# power.net
KiCad netlist of a schematic drawn in Altium Designer
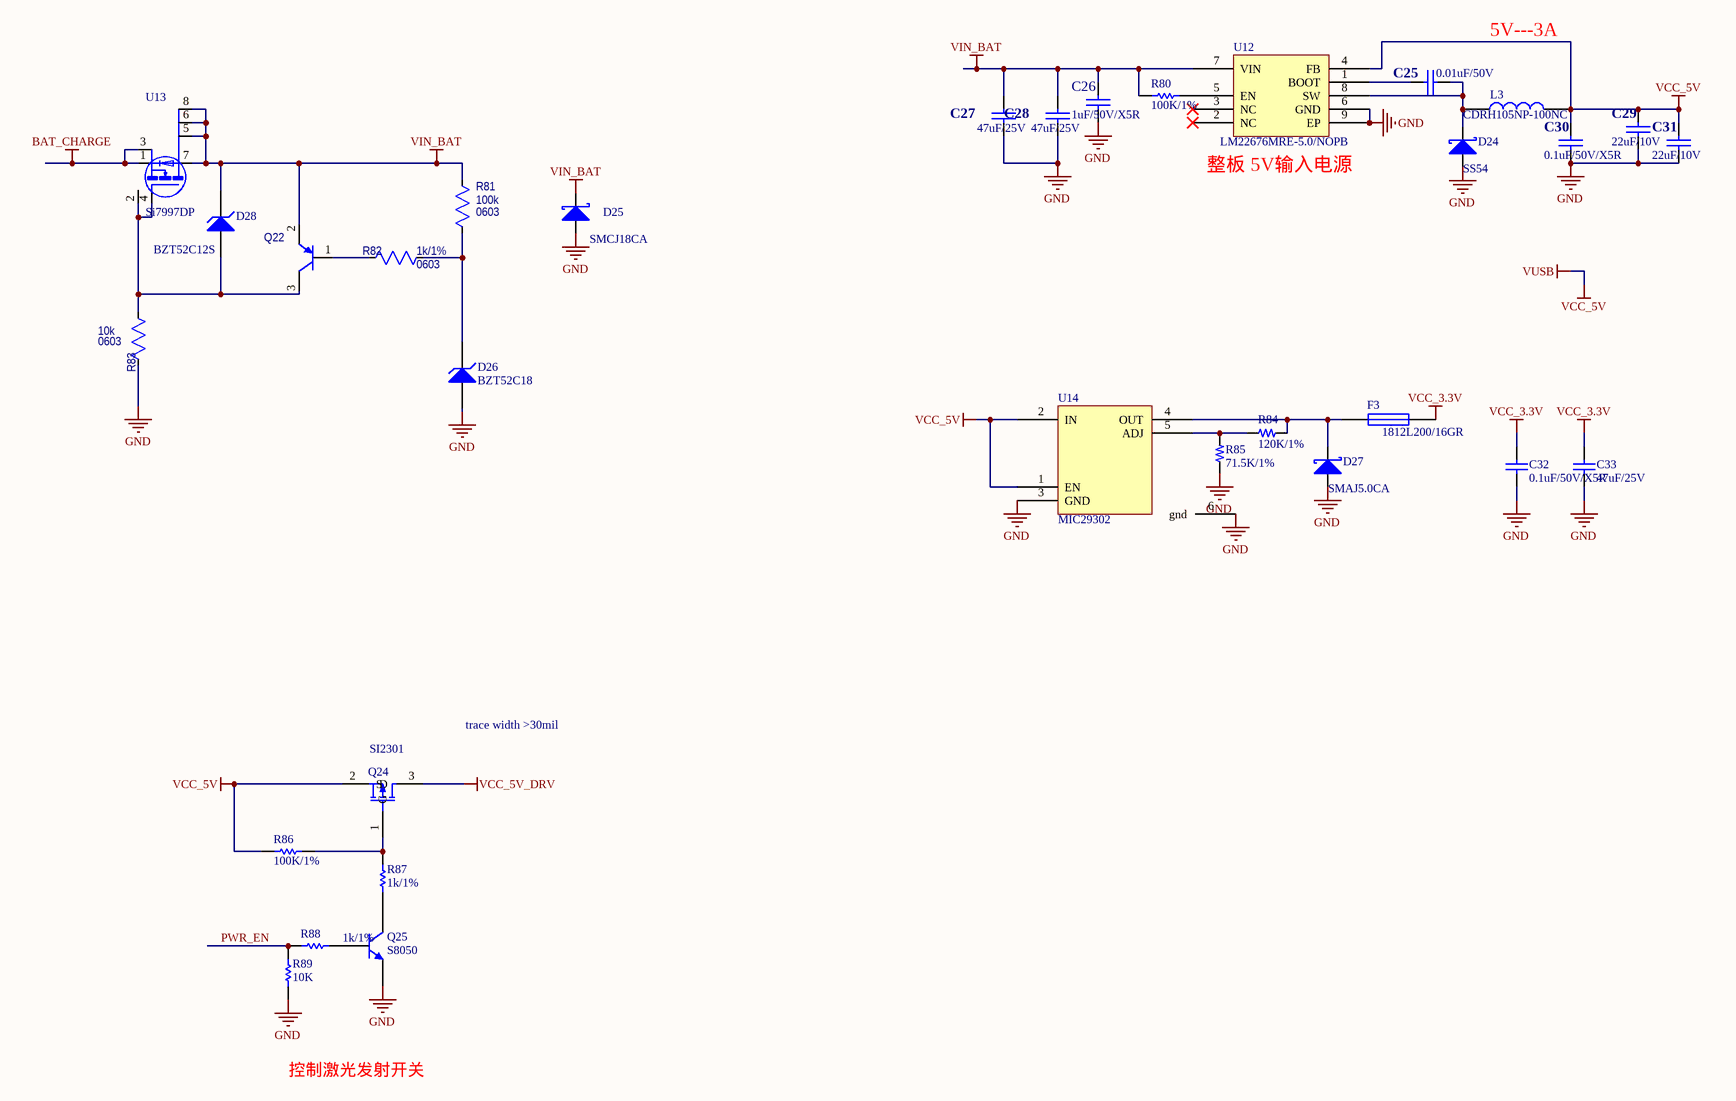
[diagram p0: power.SchDoc]

(export (version "E")
  (design (tool "Eeschema 10.0.6"))
  (components
    (comp (ref "C25")
      (value "0.01uF/50V")
      (footprint "0603C")
      (description "Capacitor")
      (libsource (lib "*") (part "CAP"))
    )
    (comp (ref "C26")
      (value "1uF/50V/X5R")
      (footprint "0603C")
      (description "Capacitor")
      (libsource (lib "*") (part "CAP"))
    )
    (comp (ref "C27")
      (value "47uF/25V")
      (footprint "1210C")
      (description "Capacitor")
      (libsource (lib "*") (part "CAP"))
    )
    (comp (ref "C28")
      (value "47uF/25V")
      (footprint "1210C")
      (description "Capacitor")
      (libsource (lib "*") (part "CAP"))
    )
    (comp (ref "C29")
      (value "22uF/10V")
      (footprint "1210C")
      (description "Capacitor")
      (libsource (lib "*") (part "CAP"))
    )
    (comp (ref "C30")
      (value "0.1uF/50V/X5R")
      (footprint "0603C")
      (description "Capacitor")
      (libsource (lib "*") (part "CAP"))
    )
    (comp (ref "C31")
      (value "22uF/10V")
      (footprint "1210C")
      (description "Capacitor")
      (libsource (lib "*") (part "CAP"))
    )
    (comp (ref "C32")
      (value "0.1uF/50V/X5R")
      (footprint "0603C")
      (description "Capacitor")
      (fields (field (name "PUBLISHER") "Altium Limited"))
      (libsource (lib "Miscellaneous Devices") (part "Cap"))
    )
    (comp (ref "C33")
      (value "47uF/25V")
      (footprint "1206C")
      (description "Capacitor")
      (fields (field (name "PUBLISHER") "Altium Limited"))
      (libsource (lib "Miscellaneous Devices") (part "Cap"))
    )
    (comp (ref "D24")
      (value "SS54")
      (footprint "SMC")
      (description "Schottky Diode")
      (libsource (lib "*") (part "DIODE S"))
    )
    (comp (ref "D25")
      (value "SMCJ18CA")
      (footprint "SMC")
      (description "Schottky Diode")
      (libsource (lib "*") (part "DIODE S"))
    )
    (comp (ref "D26")
      (value "BZT52C18")
      (footprint "sod123")
      (libsource (lib "Bogen") (part "BZT52C12S-7-F"))
    )
    (comp (ref "D27")
      (value "SMAJ5.0CA")
      (footprint "SMA")
      (description "Schottky Diode")
      (libsource (lib "*") (part "DIODE S"))
    )
    (comp (ref "D28")
      (value "BZT52C12S")
      (footprint "DIOD-SOD323-2_V")
      (description "Surface Mount Zener Diode, 12 V, -65 to 150 degC, 2-Pin SOD323, RoHS, Tape and Reel")
      (fields (field (name "MANUFACTURER") "DiodesIncorporated"))
      (libsource (lib "Bogen") (part "BZT52C12S-7-F"))
    )
    (comp (ref "F3")
      (value "1812L200/16GR")
      (footprint "1812-F")
      (description "Fuse")
      (fields (field (name "PUBLISHER") "Altium Limited"))
      (libsource (lib "Miscellaneous Devices") (part "Fuse 1"))
    )
    (comp (ref "L3") (value "CDRH105NP-100NC") (footprint "CDRH105") (libsource (lib "*") (part "INDUCTOR")))
    (comp (ref "Q22")
      (value "MMBT4403-7-F")
      (footprint "SOT23-3")
      (libsource (lib "Karl") (part "OEM_Diodes_MMBT4403"))
    )
    (comp (ref "Q24")
      (value "SI2301")
      (footprint "SOT23-3")
      (description "P-Channel MOSFET")
      (fields (field (name "PUBLISHER") "Altium Limited"))
      (libsource (lib "Miscellaneous Devices") (part "MOSFET-P"))
    )
    (comp (ref "Q25")
      (value "S8050")
      (footprint "SOT23-3")
      (description "NPN Bipolar Transistor")
      (fields (field (name "PUBLISHER") "Altium Limited"))
      (libsource (lib "Miscellaneous Devices") (part "NPN"))
    )
    (comp (ref "R80")
      (value "100K/1%")
      (footprint "0603R")
      (description "Resistor")
      (fields (field (name "PUBLISHER") "Altium Limited"))
      (libsource (lib "Miscellaneous Devices") (part "Res1"))
    )
    (comp (ref "R81")
      (value "100k")
      (footprint "0603R")
      (fields
        (field (name "PARTNUMBER") "RC0603FR-0716K9L")
        (field (name "TOLERANCE") "tol")
        (field (name "PACKAGE") "0603")
        (field (name "Comment") "100K/1%")
      )
      (libsource (lib "Karl") (part "Resistor_0603"))
    )
    (comp (ref "R82")
      (value "1k/1%")
      (footprint "0603R")
      (fields
        (field (name "PARTNUMBER") "RC0603FR-071KL")
        (field (name "TOLERANCE") "tol")
        (field (name "PACKAGE") "0603")
      )
      (libsource (lib "Karl") (part "Resistor_0603"))
    )
    (comp (ref "R83")
      (value "10k")
      (footprint "0603R")
      (fields
        (field (name "PARTNUMBER") "RC0603FR-071KL")
        (field (name "TOLERANCE") "tol")
        (field (name "PACKAGE") "0603")
      )
      (libsource (lib "Karl") (part "Resistor_0603"))
    )
    (comp (ref "R84")
      (value "120K/1%")
      (footprint "0603R")
      (description "R")
      (libsource (lib "JRJ_1") (part "R"))
    )
    (comp (ref "R85")
      (value "71.5K/1%")
      (footprint "0603R")
      (description "R")
      (libsource (lib "JRJ_1") (part "R"))
    )
    (comp (ref "R86")
      (value "100K/1%")
      (footprint "0603R")
      (description "Resistor")
      (fields (field (name "PUBLISHER") "Altium Limited"))
      (libsource (lib "Miscellaneous Devices") (part "Res1"))
    )
    (comp (ref "R87")
      (value "1k/1%")
      (footprint "0603R")
      (description "Resistor")
      (fields (field (name "PUBLISHER") "Altium Limited"))
      (libsource (lib "Miscellaneous Devices") (part "Res1"))
    )
    (comp (ref "R88")
      (value "1k/1%")
      (footprint "0603R")
      (description "Resistor")
      (fields (field (name "PUBLISHER") "Altium Limited"))
      (libsource (lib "Miscellaneous Devices") (part "Res1"))
    )
    (comp (ref "R89")
      (value "10K")
      (footprint "0603R")
      (description "Resistor")
      (fields (field (name "PUBLISHER") "Altium Limited"))
      (libsource (lib "Miscellaneous Devices") (part "Res1"))
    )
    (comp (ref "U12")
      (value "LM22676MRE-5.0/NOPB")
      (footprint "SOP127P600X168_HS-8N")
      (libsource (lib "Schlib1") (part "LM22676MR-5.0"))
    )
    (comp (ref "U13")
      (value "Si7997DP")
      (footprint "PowerPAK SO-8")
      (description "Sia430DJ")
      (libsource (lib "Schlib_20110825") (part "Si7997DP"))
    )
    (comp (ref "U14")
      (value "MIC29302")
      (footprint "TO228P1435X457-6N")
      (libsource (lib "power") (part "MIC29302"))
    )
  )
  (nets
    (net (code "1") (name "/PWR_EN") (class "Default")
      (node (ref "R88") (pin "2") (pinfunction "2_2") (pintype "passive"))
      (node (ref "R89") (pin "1") (pinfunction "1_1") (pintype "passive"))
    )
    (net (code "2") (name "BAT_CHARGE") (class "Default")
      (node (ref "U13") (pin "1") (pinfunction "S_1") (pintype "passive"))
      (node (ref "U13") (pin "3") (pinfunction "S_3") (pintype "passive"))
    )
    (net (code "3") (name "GND") (class "Default")
      (node (ref "C26") (pin "1") (pinfunction "1_1") (pintype "passive"))
      (node (ref "C27") (pin "2") (pinfunction "2_2") (pintype "passive"))
      (node (ref "C28") (pin "2") (pinfunction "2_2") (pintype "passive"))
      (node (ref "C29") (pin "2") (pinfunction "2_2") (pintype "passive"))
      (node (ref "C30") (pin "2") (pinfunction "2_2") (pintype "passive"))
      (node (ref "C31") (pin "2") (pinfunction "2_2") (pintype "passive"))
      (node (ref "C32") (pin "1") (pinfunction "1_1") (pintype "passive"))
      (node (ref "C33") (pin "1") (pinfunction "1_1") (pintype "passive"))
      (node (ref "D24") (pin "1") (pinfunction "A_1") (pintype "passive"))
      (node (ref "D25") (pin "1") (pinfunction "A_1") (pintype "passive"))
      (node (ref "D26") (pin "1") (pinfunction "A_1") (pintype "passive"))
      (node (ref "D27") (pin "1") (pinfunction "A_1") (pintype "passive"))
      (node (ref "Q25") (pin "2") (pinfunction "E_2") (pintype "passive"))
      (node (ref "R83") (pin "2") (pinfunction "2_2") (pintype "passive"))
      (node (ref "R85") (pin "1") (pintype "passive"))
      (node (ref "R89") (pin "2") (pinfunction "2_2") (pintype "passive"))
      (node (ref "U12") (pin "6") (pinfunction "GND_6") (pintype "passive"))
      (node (ref "U12") (pin "9") (pinfunction "EP_9") (pintype "passive"))
      (node (ref "U14") (pin "3") (pinfunction "GND_3") (pintype "passive"))
      (node (ref "U14") (pin "6") (pinfunction "gnd_6") (pintype "passive"))
    )
    (net (code "4") (name "Net-(D24-K)") (class "Default")
      (node (ref "C25") (pin "1") (pinfunction "1_1") (pintype "passive"))
      (node (ref "D24") (pin "2") (pinfunction "K_2") (pintype "passive"))
      (node (ref "L3") (pin "1") (pinfunction "1_1") (pintype "passive"))
      (node (ref "U12") (pin "8") (pinfunction "SW_8") (pintype "passive"))
    )
    (net (code "5") (name "Net-(D26-K)") (class "Default")
      (node (ref "D26") (pin "2") (pinfunction "K_2") (pintype "passive"))
      (node (ref "R81") (pin "1") (pinfunction "1_1") (pintype "passive"))
      (node (ref "R82") (pin "1") (pinfunction "1_1") (pintype "passive"))
    )
    (net (code "6") (name "Net-(D27-K)") (class "Default")
      (node (ref "D27") (pin "2") (pinfunction "K_2") (pintype "passive"))
      (node (ref "F3") (pin "1") (pinfunction "1_1") (pintype "passive"))
      (node (ref "R84") (pin "1") (pintype "passive"))
      (node (ref "U14") (pin "4") (pinfunction "OUT_4") (pintype "passive"))
    )
    (net (code "7") (name "Net-(D28-A)") (class "Default")
      (node (ref "D28") (pin "1") (pinfunction "A_1") (pintype "passive"))
      (node (ref "Q22") (pin "3") (pinfunction "C_3") (pintype "passive"))
      (node (ref "R83") (pin "1") (pinfunction "1_1") (pintype "passive"))
      (node (ref "U13") (pin "2") (pinfunction "G_2") (pintype "passive"))
      (node (ref "U13") (pin "4") (pinfunction "G_4") (pintype "passive"))
    )
    (net (code "8") (name "Net-(Q22-B)") (class "Default")
      (node (ref "Q22") (pin "1") (pinfunction "B_1") (pintype "passive"))
      (node (ref "R82") (pin "2") (pinfunction "2_2") (pintype "passive"))
    )
    (net (code "9") (name "Net-(Q24-G)") (class "Default")
      (node (ref "Q24") (pin "1") (pinfunction "G_1") (pintype "passive"))
      (node (ref "R86") (pin "1") (pinfunction "1_1") (pintype "passive"))
      (node (ref "R87") (pin "2") (pinfunction "2_2") (pintype "passive"))
    )
    (net (code "10") (name "Net-(Q25-B)") (class "Default")
      (node (ref "Q25") (pin "1") (pinfunction "B_1") (pintype "passive"))
      (node (ref "R88") (pin "1") (pinfunction "1_1") (pintype "passive"))
    )
    (net (code "11") (name "Net-(Q25-C)") (class "Default")
      (node (ref "Q25") (pin "3") (pinfunction "C_3") (pintype "passive"))
      (node (ref "R87") (pin "1") (pinfunction "1_1") (pintype "passive"))
    )
    (net (code "12") (name "Net-(U12-BOOT)") (class "Default")
      (node (ref "C25") (pin "2") (pinfunction "2_2") (pintype "passive"))
      (node (ref "U12") (pin "1") (pinfunction "BOOT_1") (pintype "passive"))
    )
    (net (code "13") (name "Net-(U12-EN)") (class "Default")
      (node (ref "R80") (pin "1") (pinfunction "1_1") (pintype "passive"))
      (node (ref "U12") (pin "5") (pinfunction "EN_5") (pintype "passive"))
    )
    (net (code "14") (name "Net-(U14-ADJ)") (class "Default")
      (node (ref "R84") (pin "2") (pintype "passive"))
      (node (ref "R85") (pin "2") (pintype "passive"))
      (node (ref "U14") (pin "5") (pinfunction "ADJ_5") (pintype "passive"))
    )
    (net (code "15") (name "VCC_3.3V") (class "Default")
      (node (ref "C32") (pin "2") (pinfunction "2_2") (pintype "passive"))
      (node (ref "C33") (pin "2") (pinfunction "2_2") (pintype "passive"))
      (node (ref "F3") (pin "2") (pinfunction "2_2") (pintype "passive"))
    )
    (net (code "16") (name "VCC_5V") (class "Default")
      (node (ref "C29") (pin "1") (pinfunction "1_1") (pintype "passive"))
      (node (ref "C30") (pin "1") (pinfunction "1_1") (pintype "passive"))
      (node (ref "C31") (pin "1") (pinfunction "1_1") (pintype "passive"))
      (node (ref "L3") (pin "2") (pinfunction "2_2") (pintype "passive"))
      (node (ref "Q24") (pin "2") (pinfunction "S_2") (pintype "passive"))
      (node (ref "R86") (pin "2") (pinfunction "2_2") (pintype "passive"))
      (node (ref "U12") (pin "4") (pinfunction "FB_4") (pintype "passive"))
      (node (ref "U14") (pin "1") (pinfunction "EN_1") (pintype "passive"))
      (node (ref "U14") (pin "2") (pinfunction "IN_2") (pintype "passive"))
    )
    (net (code "17") (name "VCC_5V_DRV") (class "Default")
      (node (ref "Q24") (pin "3") (pinfunction "D_3") (pintype "passive"))
    )
    (net (code "18") (name "VIN_BAT") (class "Default")
      (node (ref "C26") (pin "2") (pinfunction "2_2") (pintype "passive"))
      (node (ref "C27") (pin "1") (pinfunction "1_1") (pintype "passive"))
      (node (ref "C28") (pin "1") (pinfunction "1_1") (pintype "passive"))
      (node (ref "D25") (pin "2") (pinfunction "K_2") (pintype "passive"))
      (node (ref "D28") (pin "2") (pinfunction "K_2") (pintype "passive"))
      (node (ref "Q22") (pin "2") (pinfunction "E_2") (pintype "passive"))
      (node (ref "R80") (pin "2") (pinfunction "2_2") (pintype "passive"))
      (node (ref "R81") (pin "2") (pinfunction "2_2") (pintype "passive"))
      (node (ref "U12") (pin "7") (pinfunction "VIN_7") (pintype "passive"))
      (node (ref "U13") (pin "5") (pinfunction "D_5") (pintype "passive"))
      (node (ref "U13") (pin "6") (pinfunction "D_6") (pintype "passive"))
      (node (ref "U13") (pin "7") (pinfunction "D_7") (pintype "passive"))
      (node (ref "U13") (pin "8") (pinfunction "D_8") (pintype "passive"))
    )
    (net (code "19") (name "unconnected-(U12-NC-Pad2)") (class "Default")
      (node (ref "U12") (pin "2") (pinfunction "NC_2") (pintype "passive+no_connect"))
    )
    (net (code "20") (name "unconnected-(U12-NC-Pad3)") (class "Default")
      (node (ref "U12") (pin "3") (pinfunction "NC_3") (pintype "passive+no_connect"))
    )
  )
)
